# Schematic.net
KiCad netlist of a schematic drawn in Altium Designer
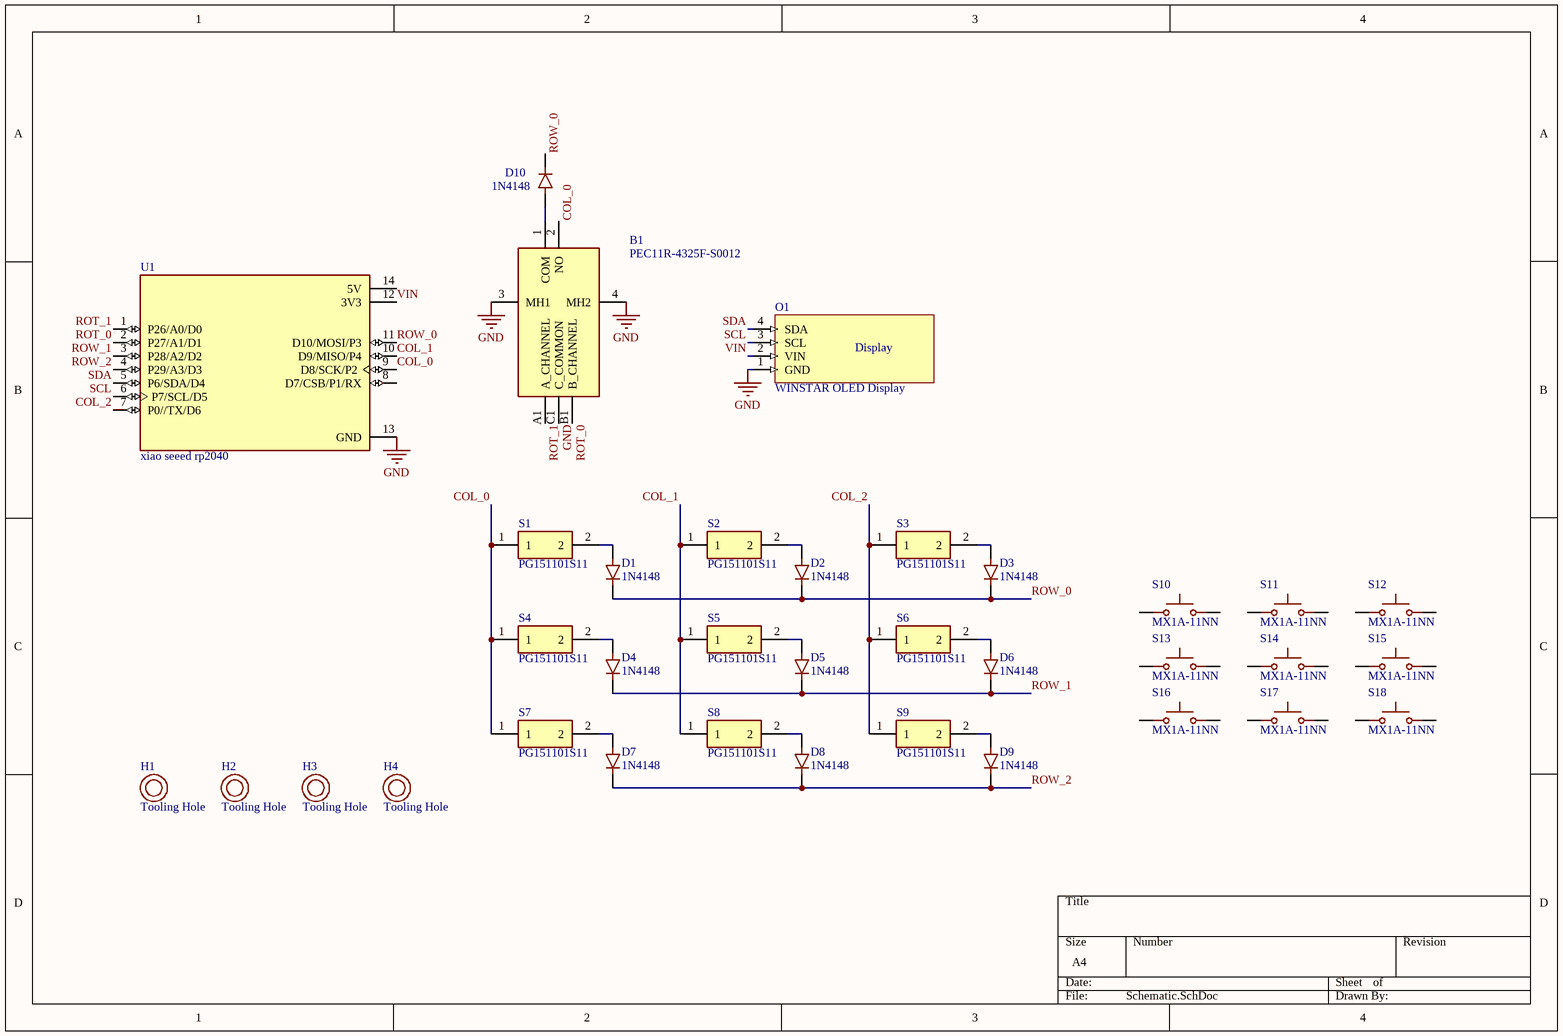
[diagram p0: Schematic.SchDoc]

(export (version "E")
  (design (tool "Eeschema 10.0.6"))
  (components
    (comp (ref "B1")
      (value "PEC11R-4325F-S0012")
      (footprint "PEC11R-4315F-S0012")
      (description "Rotary Encoder Mechanical 12 Quadrature (Incremental) Vertical")
      (fields (field (name "MOUSER PART NUMBER") "652-PEC11R4325FS0012"))
      (libsource (lib "Schematic_Lib") (part "PEC11R-4315F-S0012"))
    )
    (comp (ref "D1")
      (value "1N4148")
      (footprint "1N4148 Diode")
      (description "Diode Standard 75V 200mA Surface Mount SOD-523F")
      (fields (field (name "MF") "ON Semiconductor"))
      (libsource (lib "Schematic_Lib") (part "1N4148"))
    )
    (comp (ref "D2")
      (value "1N4148")
      (footprint "1N4148 Diode")
      (description "Diode Standard 75V 200mA Surface Mount SOD-523F")
      (fields (field (name "MF") "ON Semiconductor"))
      (libsource (lib "Schematic_Lib") (part "1N4148"))
    )
    (comp (ref "D3")
      (value "1N4148")
      (footprint "1N4148 Diode")
      (description "Diode Standard 75V 200mA Surface Mount SOD-523F")
      (fields (field (name "MF") "ON Semiconductor"))
      (libsource (lib "Schematic_Lib") (part "1N4148"))
    )
    (comp (ref "D4")
      (value "1N4148")
      (footprint "1N4148 Diode")
      (description "Diode Standard 75V 200mA Surface Mount SOD-523F")
      (fields (field (name "MF") "ON Semiconductor"))
      (libsource (lib "Schematic_Lib") (part "1N4148"))
    )
    (comp (ref "D5")
      (value "1N4148")
      (footprint "1N4148 Diode")
      (description "Diode Standard 75V 200mA Surface Mount SOD-523F")
      (fields (field (name "MF") "ON Semiconductor"))
      (libsource (lib "Schematic_Lib") (part "1N4148"))
    )
    (comp (ref "D6")
      (value "1N4148")
      (footprint "1N4148 Diode")
      (description "Diode Standard 75V 200mA Surface Mount SOD-523F")
      (fields (field (name "MF") "ON Semiconductor"))
      (libsource (lib "Schematic_Lib") (part "1N4148"))
    )
    (comp (ref "D7")
      (value "1N4148")
      (footprint "1N4148 Diode")
      (description "Diode Standard 75V 200mA Surface Mount SOD-523F")
      (fields (field (name "MF") "ON Semiconductor"))
      (libsource (lib "Schematic_Lib") (part "1N4148"))
    )
    (comp (ref "D8")
      (value "1N4148")
      (footprint "1N4148 Diode")
      (description "Diode Standard 75V 200mA Surface Mount SOD-523F")
      (fields (field (name "MF") "ON Semiconductor"))
      (libsource (lib "Schematic_Lib") (part "1N4148"))
    )
    (comp (ref "D9")
      (value "1N4148")
      (footprint "1N4148 Diode")
      (description "Diode Standard 75V 200mA Surface Mount SOD-523F")
      (fields (field (name "MF") "ON Semiconductor"))
      (libsource (lib "Schematic_Lib") (part "1N4148"))
    )
    (comp (ref "D10")
      (value "1N4148")
      (footprint "1N4148 Diode")
      (description "Diode Standard 75V 200mA Surface Mount SOD-523F")
      (fields (field (name "MF") "ON Semiconductor"))
      (libsource (lib "Schematic_Lib") (part "1N4148"))
    )
    (comp (ref "H1")
      (value "Tooling Hole")
      (footprint "Tooling Hole")
      (libsource (lib "Schematic_Lib") (part "Tooling Hole"))
    )
    (comp (ref "H2")
      (value "Tooling Hole")
      (footprint "Tooling Hole")
      (libsource (lib "Schematic_Lib") (part "Tooling Hole"))
    )
    (comp (ref "H3")
      (value "Tooling Hole")
      (footprint "Tooling Hole")
      (libsource (lib "Schematic_Lib") (part "Tooling Hole"))
    )
    (comp (ref "H4")
      (value "Tooling Hole")
      (footprint "Tooling Hole")
      (libsource (lib "Schematic_Lib") (part "Tooling Hole"))
    )
    (comp (ref "O1")
      (value "WINSTAR OLED Display")
      (footprint "WINSTAR OLED Display")
      (description "WEA012832FWPP3N00000")
      (libsource (lib "Schematic_Lib") (part "WINSTAR OLED Display"))
    )
    (comp (ref "S1")
      (value "PG151101S11")
      (footprint "SW_PG151101S11")
      (fields (field (name "MF") "Kailh"))
      (libsource (lib "Schematic_Lib") (part "PG151101S11"))
    )
    (comp (ref "S2")
      (value "PG151101S11")
      (footprint "SW_PG151101S11")
      (fields (field (name "MF") "Kailh"))
      (libsource (lib "Schematic_Lib") (part "PG151101S11"))
    )
    (comp (ref "S3")
      (value "PG151101S11")
      (footprint "SW_PG151101S11")
      (fields (field (name "MF") "Kailh"))
      (libsource (lib "Schematic_Lib") (part "PG151101S11"))
    )
    (comp (ref "S4")
      (value "PG151101S11")
      (footprint "SW_PG151101S11")
      (fields (field (name "MF") "Kailh"))
      (libsource (lib "Schematic_Lib") (part "PG151101S11"))
    )
    (comp (ref "S5")
      (value "PG151101S11")
      (footprint "SW_PG151101S11")
      (fields (field (name "MF") "Kailh"))
      (libsource (lib "Schematic_Lib") (part "PG151101S11"))
    )
    (comp (ref "S6")
      (value "PG151101S11")
      (footprint "SW_PG151101S11")
      (fields (field (name "MF") "Kailh"))
      (libsource (lib "Schematic_Lib") (part "PG151101S11"))
    )
    (comp (ref "S7")
      (value "PG151101S11")
      (footprint "SW_PG151101S11")
      (fields (field (name "MF") "Kailh"))
      (libsource (lib "Schematic_Lib") (part "PG151101S11"))
    )
    (comp (ref "S8")
      (value "PG151101S11")
      (footprint "SW_PG151101S11")
      (fields (field (name "MF") "Kailh"))
      (libsource (lib "Schematic_Lib") (part "PG151101S11"))
    )
    (comp (ref "S9")
      (value "PG151101S11")
      (footprint "SW_PG151101S11")
      (fields (field (name "MF") "Kailh"))
      (libsource (lib "Schematic_Lib") (part "PG151101S11"))
    )
    (comp (ref "S10")
      (value "MX1A-11NN")
      (footprint "SW_MX1A-11NN")
      (fields (field (name "MF") "Cherry"))
      (libsource (lib "Schematic_Lib") (part "MX1A-11NN"))
    )
    (comp (ref "S11")
      (value "MX1A-11NN")
      (footprint "SW_MX1A-11NN")
      (fields (field (name "MF") "Cherry"))
      (libsource (lib "Schematic_Lib") (part "MX1A-11NN"))
    )
    (comp (ref "S12")
      (value "MX1A-11NN")
      (footprint "SW_MX1A-11NN")
      (fields (field (name "MF") "Cherry"))
      (libsource (lib "Schematic_Lib") (part "MX1A-11NN"))
    )
    (comp (ref "S13")
      (value "MX1A-11NN")
      (footprint "SW_MX1A-11NN")
      (fields (field (name "MF") "Cherry"))
      (libsource (lib "Schematic_Lib") (part "MX1A-11NN"))
    )
    (comp (ref "S14")
      (value "MX1A-11NN")
      (footprint "SW_MX1A-11NN")
      (fields (field (name "MF") "Cherry"))
      (libsource (lib "Schematic_Lib") (part "MX1A-11NN"))
    )
    (comp (ref "S15")
      (value "MX1A-11NN")
      (footprint "SW_MX1A-11NN")
      (fields (field (name "MF") "Cherry"))
      (libsource (lib "Schematic_Lib") (part "MX1A-11NN"))
    )
    (comp (ref "S16")
      (value "MX1A-11NN")
      (footprint "SW_MX1A-11NN")
      (fields (field (name "MF") "Cherry"))
      (libsource (lib "Schematic_Lib") (part "MX1A-11NN"))
    )
    (comp (ref "S17")
      (value "MX1A-11NN")
      (footprint "SW_MX1A-11NN")
      (fields (field (name "MF") "Cherry"))
      (libsource (lib "Schematic_Lib") (part "MX1A-11NN"))
    )
    (comp (ref "S18")
      (value "MX1A-11NN")
      (footprint "SW_MX1A-11NN")
      (fields (field (name "MF") "Cherry"))
      (libsource (lib "Schematic_Lib") (part "MX1A-11NN"))
    )
    (comp (ref "U1")
      (value "xiao seeed rp2040")
      (footprint "MODULE_102010428")
      (description "RP2040 XIAO RP2040 series ARMÂ® CortexÂ®-M0+ MCU 32-Bit Embedded Evaluation Board")
      (fields (field (name "MF") "Seeed Technology Co., Ltd") (field (name "MP") "102010428"))
      (libsource (lib "Schematic_Lib") (part "xiao seeed rp2040"))
    )
  )
  (nets
    (net (code "1") (name "/COL_0") (class "Default")
      (node (ref "B1") (pin "2") (pinfunction "NO_2") (pintype "passive"))
      (node (ref "S1") (pin "1") (pinfunction "1_1") (pintype "passive"))
      (node (ref "S4") (pin "1") (pinfunction "1_1") (pintype "passive"))
      (node (ref "S7") (pin "1") (pinfunction "1_1") (pintype "passive"))
      (node (ref "U1") (pin "9") (pinfunction "D8/SCK/P2_9") (pintype "bidirectional"))
    )
    (net (code "2") (name "/COL_1") (class "Default")
      (node (ref "S2") (pin "1") (pinfunction "1_1") (pintype "passive"))
      (node (ref "S5") (pin "1") (pinfunction "1_1") (pintype "passive"))
      (node (ref "S8") (pin "1") (pinfunction "1_1") (pintype "passive"))
      (node (ref "U1") (pin "10") (pinfunction "D9/MISO/P4_10") (pintype "bidirectional"))
    )
    (net (code "3") (name "/COL_2") (class "Default")
      (node (ref "S3") (pin "1") (pinfunction "1_1") (pintype "passive"))
      (node (ref "S6") (pin "1") (pinfunction "1_1") (pintype "passive"))
      (node (ref "S9") (pin "1") (pinfunction "1_1") (pintype "passive"))
      (node (ref "U1") (pin "7") (pinfunction "P0//TX/D6_7") (pintype "bidirectional"))
    )
    (net (code "4") (name "/ROT_0") (class "Default")
      (node (ref "B1") (pin "B1") (pinfunction "B_CHANNEL_B1") (pintype "passive"))
      (node (ref "U1") (pin "2") (pinfunction "P27/A1/D1_2") (pintype "bidirectional"))
    )
    (net (code "5") (name "/ROT_1") (class "Default")
      (node (ref "B1") (pin "A1") (pinfunction "A_CHANNEL_A1") (pintype "passive"))
      (node (ref "U1") (pin "1") (pinfunction "P26/A0/D0_1") (pintype "bidirectional"))
    )
    (net (code "6") (name "/ROW_0") (class "Default")
      (node (ref "D1") (pin "K") (pinfunction "K_K") (pintype "passive"))
      (node (ref "D10") (pin "K") (pinfunction "K_K") (pintype "passive"))
      (node (ref "D2") (pin "K") (pinfunction "K_K") (pintype "passive"))
      (node (ref "D3") (pin "K") (pinfunction "K_K") (pintype "passive"))
      (node (ref "U1") (pin "11") (pinfunction "D10/MOSI/P3_11") (pintype "bidirectional"))
    )
    (net (code "7") (name "/ROW_1") (class "Default")
      (node (ref "D4") (pin "K") (pinfunction "K_K") (pintype "passive"))
      (node (ref "D5") (pin "K") (pinfunction "K_K") (pintype "passive"))
      (node (ref "D6") (pin "K") (pinfunction "K_K") (pintype "passive"))
      (node (ref "U1") (pin "3") (pinfunction "P28/A2/D2_3") (pintype "bidirectional"))
    )
    (net (code "8") (name "/ROW_2") (class "Default")
      (node (ref "D7") (pin "K") (pinfunction "K_K") (pintype "passive"))
      (node (ref "D8") (pin "K") (pinfunction "K_K") (pintype "passive"))
      (node (ref "D9") (pin "K") (pinfunction "K_K") (pintype "passive"))
      (node (ref "U1") (pin "4") (pinfunction "P29/A3/D3_4") (pintype "bidirectional"))
    )
    (net (code "9") (name "/SCL") (class "Default")
      (node (ref "O1") (pin "3") (pinfunction "SCL_3") (pintype "input"))
      (node (ref "U1") (pin "6") (pinfunction "P7/SCL/D5_6") (pintype "bidirectional"))
    )
    (net (code "10") (name "/SDA") (class "Default")
      (node (ref "O1") (pin "4") (pinfunction "SDA_4") (pintype "input"))
      (node (ref "U1") (pin "5") (pinfunction "P6/SDA/D4_5") (pintype "bidirectional"))
    )
    (net (code "11") (name "/VIN") (class "Default")
      (node (ref "O1") (pin "2") (pinfunction "VIN_2") (pintype "input"))
      (node (ref "U1") (pin "12") (pinfunction "3V3_12") (pintype "power_in"))
    )
    (net (code "12") (name "GND") (class "Default")
      (node (ref "B1") (pin "3") (pinfunction "MH1_3") (pintype "passive"))
      (node (ref "B1") (pin "4") (pinfunction "MH2_4") (pintype "passive"))
      (node (ref "B1") (pin "C1") (pinfunction "C_COMMON_C1") (pintype "passive"))
      (node (ref "O1") (pin "1") (pinfunction "GND_1") (pintype "input"))
      (node (ref "U1") (pin "13") (pinfunction "GND_13") (pintype "power_in"))
    )
    (net (code "13") (name "Net-(B1-COM)") (class "Default")
      (node (ref "B1") (pin "1") (pinfunction "COM_1") (pintype "passive"))
      (node (ref "D10") (pin "A") (pinfunction "A_A") (pintype "passive"))
    )
    (net (code "14") (name "Net-(D1-PadA)") (class "Default")
      (node (ref "D1") (pin "A") (pinfunction "A_A") (pintype "passive"))
      (node (ref "S1") (pin "2") (pinfunction "2_2") (pintype "passive"))
    )
    (net (code "15") (name "Net-(D2-PadA)") (class "Default")
      (node (ref "D2") (pin "A") (pinfunction "A_A") (pintype "passive"))
      (node (ref "S2") (pin "2") (pinfunction "2_2") (pintype "passive"))
    )
    (net (code "16") (name "Net-(D3-PadA)") (class "Default")
      (node (ref "D3") (pin "A") (pinfunction "A_A") (pintype "passive"))
      (node (ref "S3") (pin "2") (pinfunction "2_2") (pintype "passive"))
    )
    (net (code "17") (name "Net-(D4-PadA)") (class "Default")
      (node (ref "D4") (pin "A") (pinfunction "A_A") (pintype "passive"))
      (node (ref "S4") (pin "2") (pinfunction "2_2") (pintype "passive"))
    )
    (net (code "18") (name "Net-(D5-PadA)") (class "Default")
      (node (ref "D5") (pin "A") (pinfunction "A_A") (pintype "passive"))
      (node (ref "S5") (pin "2") (pinfunction "2_2") (pintype "passive"))
    )
    (net (code "19") (name "Net-(D6-PadA)") (class "Default")
      (node (ref "D6") (pin "A") (pinfunction "A_A") (pintype "passive"))
      (node (ref "S6") (pin "2") (pinfunction "2_2") (pintype "passive"))
    )
    (net (code "20") (name "Net-(D7-PadA)") (class "Default")
      (node (ref "D7") (pin "A") (pinfunction "A_A") (pintype "passive"))
      (node (ref "S7") (pin "2") (pinfunction "2_2") (pintype "passive"))
    )
    (net (code "21") (name "Net-(D8-PadA)") (class "Default")
      (node (ref "D8") (pin "A") (pinfunction "A_A") (pintype "passive"))
      (node (ref "S8") (pin "2") (pinfunction "2_2") (pintype "passive"))
    )
    (net (code "22") (name "Net-(D9-PadA)") (class "Default")
      (node (ref "D9") (pin "A") (pinfunction "A_A") (pintype "passive"))
      (node (ref "S9") (pin "2") (pinfunction "2_2") (pintype "passive"))
    )
    (net (code "23") (name "unconnected-(S10-Pad1)") (class "Default")
      (node (ref "S10") (pin "1") (pinfunction "1_1") (pintype "passive"))
    )
    (net (code "24") (name "unconnected-(S10-Pad2)") (class "Default")
      (node (ref "S10") (pin "2") (pinfunction "2_2") (pintype "passive"))
    )
    (net (code "25") (name "unconnected-(S11-Pad1)") (class "Default")
      (node (ref "S11") (pin "1") (pinfunction "1_1") (pintype "passive"))
    )
    (net (code "26") (name "unconnected-(S11-Pad2)") (class "Default")
      (node (ref "S11") (pin "2") (pinfunction "2_2") (pintype "passive"))
    )
    (net (code "27") (name "unconnected-(S12-Pad1)") (class "Default")
      (node (ref "S12") (pin "1") (pinfunction "1_1") (pintype "passive"))
    )
    (net (code "28") (name "unconnected-(S12-Pad2)") (class "Default")
      (node (ref "S12") (pin "2") (pinfunction "2_2") (pintype "passive"))
    )
    (net (code "29") (name "unconnected-(S13-Pad1)") (class "Default")
      (node (ref "S13") (pin "1") (pinfunction "1_1") (pintype "passive"))
    )
    (net (code "30") (name "unconnected-(S13-Pad2)") (class "Default")
      (node (ref "S13") (pin "2") (pinfunction "2_2") (pintype "passive"))
    )
    (net (code "31") (name "unconnected-(S14-Pad1)") (class "Default")
      (node (ref "S14") (pin "1") (pinfunction "1_1") (pintype "passive"))
    )
    (net (code "32") (name "unconnected-(S14-Pad2)") (class "Default")
      (node (ref "S14") (pin "2") (pinfunction "2_2") (pintype "passive"))
    )
    (net (code "33") (name "unconnected-(S15-Pad1)") (class "Default")
      (node (ref "S15") (pin "1") (pinfunction "1_1") (pintype "passive"))
    )
    (net (code "34") (name "unconnected-(S15-Pad2)") (class "Default")
      (node (ref "S15") (pin "2") (pinfunction "2_2") (pintype "passive"))
    )
    (net (code "35") (name "unconnected-(S16-Pad1)") (class "Default")
      (node (ref "S16") (pin "1") (pinfunction "1_1") (pintype "passive"))
    )
    (net (code "36") (name "unconnected-(S16-Pad2)") (class "Default")
      (node (ref "S16") (pin "2") (pinfunction "2_2") (pintype "passive"))
    )
    (net (code "37") (name "unconnected-(S17-Pad1)") (class "Default")
      (node (ref "S17") (pin "1") (pinfunction "1_1") (pintype "passive"))
    )
    (net (code "38") (name "unconnected-(S17-Pad2)") (class "Default")
      (node (ref "S17") (pin "2") (pinfunction "2_2") (pintype "passive"))
    )
    (net (code "39") (name "unconnected-(S18-Pad1)") (class "Default")
      (node (ref "S18") (pin "1") (pinfunction "1_1") (pintype "passive"))
    )
    (net (code "40") (name "unconnected-(S18-Pad2)") (class "Default")
      (node (ref "S18") (pin "2") (pinfunction "2_2") (pintype "passive"))
    )
    (net (code "41") (name "unconnected-(U1-5V-Pad14)") (class "Default")
      (node (ref "U1") (pin "14") (pinfunction "5V_14") (pintype "power_in"))
    )
    (net (code "42") (name "unconnected-(U1-D7{slash}CSB{slash}P1{slash}RX-Pad8)") (class "Default")
      (node (ref "U1") (pin "8") (pinfunction "D7/CSB/P1/RX_8") (pintype "bidirectional"))
    )
  )
)
